# Regulators_and_Buck_Converters.net
KiCad netlist of a schematic drawn in Altium Designer
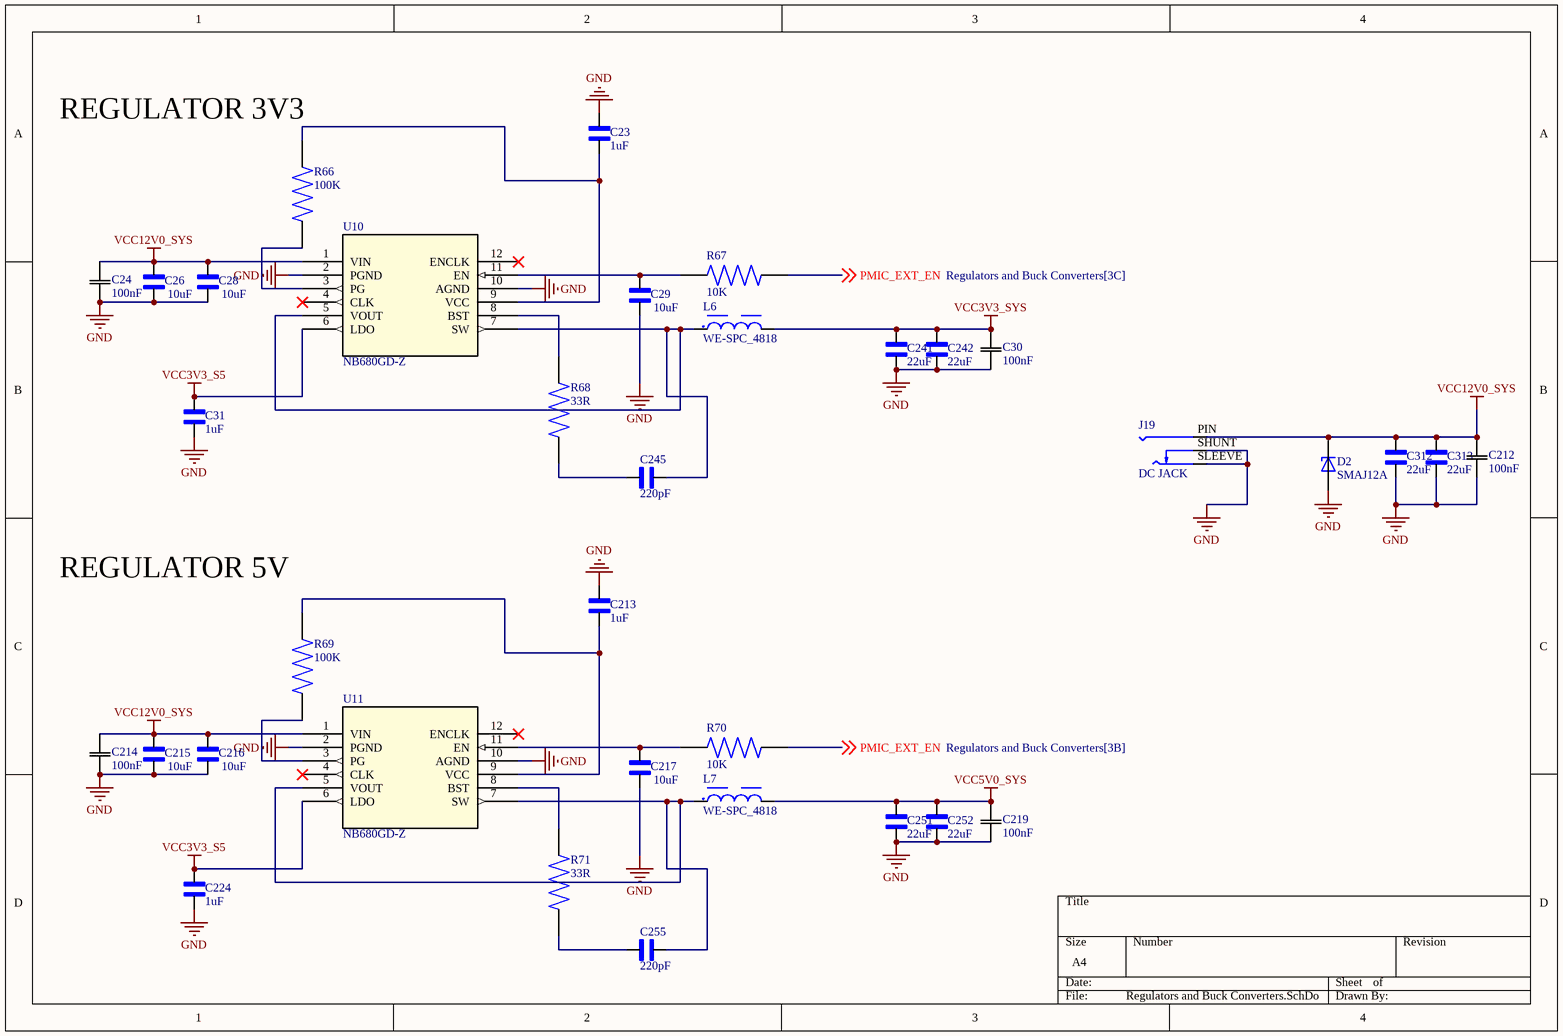
[diagram p0: Regulators and Buck Converters.SchDoc]

(export (version "E")
  (design (tool "Eeschema 10.0.6"))
  (components
    (comp (ref "C23")
      (value "1uF")
      (footprint "CAPC1005X56N")
      (description "1 ÂµF Â±10% 10V Ceramic Capacitor X5R 0402 (1005 Metric)")
      (fields (field (name "MF") "AVX") (field (name "MP") "0402ZD105KAT4A"))
      (libsource (lib "0402ZD105KAT4A") (part "0402ZD105KAT4A"))
    )
    (comp (ref "C24")
      (value "100nF")
      (footprint "CAP_1005_TDK")
      (description "Description")
      (fields
        (field (name "MANUFACTURER_PART_NUMBER") "C1005X7R1H104M050BB")
        (field (name "COPYRIGHT") "Copyright (C) 2025 Ultra Librarian. All rights reserved.")
      )
      (libsource (lib "C1005X7R1H104M050BB") (part "C1005X7R1H104M050BB"))
    )
    (comp (ref "C26")
      (value "10uF")
      (footprint "CAPC1005X70N")
      (description "10 ÂµF Â±20% 6.3V Ceramic Capacitor X5R 0402 (1005 Metric)")
      (fields (field (name "MF") "Samsung") (field (name "MP") "CL05A106MQ5NUNC"))
      (libsource (lib "CL05A106MQ5NUNC") (part "CL05A106MQ5NUNC"))
    )
    (comp (ref "C28")
      (value "10uF")
      (footprint "CAPC1005X70N")
      (description "10 ÂµF Â±20% 6.3V Ceramic Capacitor X5R 0402 (1005 Metric)")
      (fields (field (name "MF") "Samsung") (field (name "MP") "CL05A106MQ5NUNC"))
      (libsource (lib "CL05A106MQ5NUNC") (part "CL05A106MQ5NUNC"))
    )
    (comp (ref "C29")
      (value "10uF")
      (footprint "CAPC1005X70N")
      (description "10 ÂµF Â±20% 6.3V Ceramic Capacitor X5R 0402 (1005 Metric)")
      (fields (field (name "MF") "Samsung") (field (name "MP") "CL05A106MQ5NUNC"))
      (libsource (lib "CL05A106MQ5NUNC") (part "CL05A106MQ5NUNC"))
    )
    (comp (ref "C30")
      (value "100nF")
      (footprint "CAP_1005_TDK")
      (description "Description")
      (fields
        (field (name "MANUFACTURER_PART_NUMBER") "C1005X7R1H104M050BB")
        (field (name "COPYRIGHT") "Copyright (C) 2025 Ultra Librarian. All rights reserved.")
      )
      (libsource (lib "C1005X7R1H104M050BB") (part "C1005X7R1H104M050BB"))
    )
    (comp (ref "C31")
      (value "1uF")
      (footprint "CAPC1005X56N")
      (description "1 ÂµF Â±10% 10V Ceramic Capacitor X5R 0402 (1005 Metric)")
      (fields (field (name "MF") "AVX") (field (name "MP") "0402ZD105KAT4A"))
      (libsource (lib "0402ZD105KAT4A") (part "0402ZD105KAT4A"))
    )
    (comp (ref "C212")
      (value "100nF")
      (footprint "CAP_1005_TDK")
      (description "Description")
      (fields
        (field (name "MANUFACTURER_PART_NUMBER") "C1005X7R1H104M050BB")
        (field (name "COPYRIGHT") "Copyright (C) 2025 Ultra Librarian. All rights reserved.")
      )
      (libsource (lib "C1005X7R1H104M050BB") (part "C1005X7R1H104M050BB"))
    )
    (comp (ref "C213")
      (value "1uF")
      (footprint "CAPC1005X56N")
      (description "1 ÂµF Â±10% 10V Ceramic Capacitor X5R 0402 (1005 Metric)")
      (fields (field (name "MF") "AVX") (field (name "MP") "0402ZD105KAT4A"))
      (libsource (lib "0402ZD105KAT4A") (part "0402ZD105KAT4A"))
    )
    (comp (ref "C214")
      (value "100nF")
      (footprint "CAP_1005_TDK")
      (description "Description")
      (fields
        (field (name "MANUFACTURER_PART_NUMBER") "C1005X7R1H104M050BB")
        (field (name "COPYRIGHT") "Copyright (C) 2025 Ultra Librarian. All rights reserved.")
      )
      (libsource (lib "C1005X7R1H104M050BB") (part "C1005X7R1H104M050BB"))
    )
    (comp (ref "C215")
      (value "10uF")
      (footprint "CAPC1005X70N")
      (description "10 ÂµF Â±20% 6.3V Ceramic Capacitor X5R 0402 (1005 Metric)")
      (fields (field (name "MF") "Samsung") (field (name "MP") "CL05A106MQ5NUNC"))
      (libsource (lib "CL05A106MQ5NUNC") (part "CL05A106MQ5NUNC"))
    )
    (comp (ref "C216")
      (value "10uF")
      (footprint "CAPC1005X70N")
      (description "10 ÂµF Â±20% 6.3V Ceramic Capacitor X5R 0402 (1005 Metric)")
      (fields (field (name "MF") "Samsung") (field (name "MP") "CL05A106MQ5NUNC"))
      (libsource (lib "CL05A106MQ5NUNC") (part "CL05A106MQ5NUNC"))
    )
    (comp (ref "C217")
      (value "10uF")
      (footprint "CAPC1005X70N")
      (description "10 ÂµF Â±20% 6.3V Ceramic Capacitor X5R 0402 (1005 Metric)")
      (fields (field (name "MF") "Samsung") (field (name "MP") "CL05A106MQ5NUNC"))
      (libsource (lib "CL05A106MQ5NUNC") (part "CL05A106MQ5NUNC"))
    )
    (comp (ref "C219")
      (value "100nF")
      (footprint "CAP_1005_TDK")
      (description "Description")
      (fields
        (field (name "MANUFACTURER_PART_NUMBER") "C1005X7R1H104M050BB")
        (field (name "COPYRIGHT") "Copyright (C) 2025 Ultra Librarian. All rights reserved.")
      )
      (libsource (lib "C1005X7R1H104M050BB") (part "C1005X7R1H104M050BB"))
    )
    (comp (ref "C224")
      (value "1uF")
      (footprint "CAPC1005X56N")
      (description "1 ÂµF Â±10% 10V Ceramic Capacitor X5R 0402 (1005 Metric)")
      (fields (field (name "MF") "AVX") (field (name "MP") "0402ZD105KAT4A"))
      (libsource (lib "0402ZD105KAT4A") (part "0402ZD105KAT4A"))
    )
    (comp (ref "C241")
      (value "22uF")
      (footprint "CAPC2012X140N")
      (description "Capacitor, Ceramic, Cap, 22.0pF, Tol 5%, SMT, 50V, C0G ¦ KEMET C0805C220J5GACTU")
      (fields (field (name "MF") "KEMET") (field (name "MP") "C0805C220J5GACTU"))
      (libsource (lib "C0805C220J5GACTU") (part "C0805C220J5GACTU"))
    )
    (comp (ref "C242")
      (value "22uF")
      (footprint "CAPC2012X140N")
      (description "Capacitor, Ceramic, Cap, 22.0pF, Tol 5%, SMT, 50V, C0G ¦ KEMET C0805C220J5GACTU")
      (fields (field (name "MF") "KEMET") (field (name "MP") "C0805C220J5GACTU"))
      (libsource (lib "C0805C220J5GACTU") (part "C0805C220J5GACTU"))
    )
    (comp (ref "C245")
      (value "220pF")
      (footprint "CAPC1608X90")
      (description "220 pF Â±10% 16V Ceramic Capacitor X7R 0603 (1608 Metric)")
      (fields (field (name "MF") "Yageo") (field (name "MP") "CC0603KRX7R7BB221"))
      (libsource (lib "CC0603KRX7R7BB221") (part "CC0603KRX7R7BB221"))
    )
    (comp (ref "C251")
      (value "22uF")
      (footprint "CAPC2012X140N")
      (description "Capacitor, Ceramic, Cap, 22.0pF, Tol 5%, SMT, 50V, C0G ¦ KEMET C0805C220J5GACTU")
      (fields (field (name "MF") "KEMET") (field (name "MP") "C0805C220J5GACTU"))
      (libsource (lib "C0805C220J5GACTU") (part "C0805C220J5GACTU"))
    )
    (comp (ref "C252")
      (value "22uF")
      (footprint "CAPC2012X140N")
      (description "Capacitor, Ceramic, Cap, 22.0pF, Tol 5%, SMT, 50V, C0G ¦ KEMET C0805C220J5GACTU")
      (fields (field (name "MF") "KEMET") (field (name "MP") "C0805C220J5GACTU"))
      (libsource (lib "C0805C220J5GACTU") (part "C0805C220J5GACTU"))
    )
    (comp (ref "C255")
      (value "220pF")
      (footprint "CAPC1608X90")
      (description "220 pF Â±10% 16V Ceramic Capacitor X7R 0603 (1608 Metric)")
      (fields (field (name "MF") "Yageo") (field (name "MP") "CC0603KRX7R7BB221"))
      (libsource (lib "CC0603KRX7R7BB221") (part "CC0603KRX7R7BB221"))
    )
    (comp (ref "C312")
      (value "22uF")
      (footprint "CAPC2012X140N")
      (description "Capacitor, Ceramic, Cap, 22.0pF, Tol 5%, SMT, 50V, C0G ¦ KEMET C0805C220J5GACTU")
      (fields (field (name "MF") "KEMET") (field (name "MP") "C0805C220J5GACTU"))
      (libsource (lib "C0805C220J5GACTU") (part "C0805C220J5GACTU"))
    )
    (comp (ref "C313")
      (value "22uF")
      (footprint "CAPC2012X140N")
      (description "Capacitor, Ceramic, Cap, 22.0pF, Tol 5%, SMT, 50V, C0G ¦ KEMET C0805C220J5GACTU")
      (fields (field (name "MF") "KEMET") (field (name "MP") "C0805C220J5GACTU"))
      (libsource (lib "C0805C220J5GACTU") (part "C0805C220J5GACTU"))
    )
    (comp (ref "D2")
      (value "SMAJ12A")
      (footprint "DIOM4325X250N")
      (description "400W, 14V, 5%, Unidirectional, TVS")
      (fields (field (name "MF") "Taiwan Semiconductor"))
      (libsource (lib "SMAJ12A") (part "SMAJ12A"))
    )
    (comp (ref "J19")
      (value "DC JACK")
      (footprint "SWITCHCRAFT_RASM712PX")
      (description "Conn;AV;DC,Power;Jack;2.5mmPinSize;RtAngle;DCSeries;SMTMount ¦ Switchcraft RASM712PX")
      (fields (field (name "MF") "Switchcraft Inc.") (field (name "MP") "RASM712PX"))
      (libsource (lib "RASM712PX") (part "RASM712PX"))
    )
    (comp (ref "L6")
      (value "WE-SPC_4818")
      (footprint "WE-SPC_4818")
      (description "10 ÂµH Shielded Drum Core, Wirewound Inductor 900 mA 248mOhm Max 1919 (4848 Metric)")
      (fields (field (name "MF") "WÃ¼rth Elektronik") (field (name "MP") "74408941100"))
      (libsource (lib "WE-SPC_4818") (part "WE-SPC_4818"))
    )
    (comp (ref "L7")
      (value "WE-SPC_4818")
      (footprint "WE-SPC_4818")
      (description "10 ÂµH Shielded Drum Core, Wirewound Inductor 900 mA 248mOhm Max 1919 (4848 Metric)")
      (fields (field (name "MF") "WÃ¼rth Elektronik") (field (name "MP") "74408941100"))
      (libsource (lib "WE-SPC_4818") (part "WE-SPC_4818"))
    )
    (comp (ref "R66")
      (value "100K")
      (footprint "RES_ERA3ARB103V")
      (fields (field (name "MP") "ERA3ARB103V"))
      (libsource (lib "ERA3ARB103V") (part "ERA3ARB103V"))
    )
    (comp (ref "R67")
      (value "10K")
      (footprint "RES_ERA3ARB103V")
      (fields (field (name "MP") "ERA3ARB103V"))
      (libsource (lib "ERA3ARB103V") (part "ERA3ARB103V"))
    )
    (comp (ref "R68")
      (value "33R")
      (footprint "RES_ERA6AHD330V")
      (fields (field (name "MP") "ERA6AHD330V"))
      (libsource (lib "ERA6AHD330V") (part "ERA6AHD330V"))
    )
    (comp (ref "R69")
      (value "100K")
      (footprint "RES_ERA3ARB103V")
      (fields (field (name "MP") "ERA3ARB103V"))
      (libsource (lib "ERA3ARB103V") (part "ERA3ARB103V"))
    )
    (comp (ref "R70")
      (value "10K")
      (footprint "RES_ERA3ARB103V")
      (fields (field (name "MP") "ERA3ARB103V"))
      (libsource (lib "ERA3ARB103V") (part "ERA3ARB103V"))
    )
    (comp (ref "R71")
      (value "33R")
      (footprint "RES_ERA6AHD330V")
      (fields (field (name "MP") "ERA6AHD330V"))
      (libsource (lib "ERA6AHD330V") (part "ERA6AHD330V"))
    )
    (comp (ref "U10")
      (value "NB680GD-Z")
      (footprint "QFN-12_NB680_MNP")
      (description "Wide Vin 4.8-26V Low Iq High Current Fixed 3.3V-8A Synchronous Buck Converter with 100mA LDO")
      (fields (field (name "COPYRIGHT") "Copyright (C) 2026 Ultra Librarian. All rights reserved."))
      (libsource (lib "NB680GD-Z") (part "NB680GD-Z"))
    )
    (comp (ref "U11")
      (value "NB680GD-Z")
      (footprint "QFN-12_NB680_MNP")
      (description "Wide Vin 4.8-26V Low Iq High Current Fixed 3.3V-8A Synchronous Buck Converter with 100mA LDO")
      (fields (field (name "COPYRIGHT") "Copyright (C) 2026 Ultra Librarian. All rights reserved."))
      (libsource (lib "NB680GD-Z") (part "NB680GD-Z"))
    )
  )
  (nets
    (net (code "1") (name "GND") (class "Default")
      (node (ref "C212") (pin "1") (pinfunction "1_1") (pintype "passive"))
      (node (ref "C213") (pin "2") (pinfunction "2_2") (pintype "passive"))
      (node (ref "C214") (pin "1") (pinfunction "1_1") (pintype "passive"))
      (node (ref "C215") (pin "1") (pinfunction "1_1") (pintype "passive"))
      (node (ref "C216") (pin "1") (pinfunction "1_1") (pintype "passive"))
      (node (ref "C217") (pin "1") (pinfunction "1_1") (pintype "passive"))
      (node (ref "C219") (pin "1") (pinfunction "1_1") (pintype "passive"))
      (node (ref "C224") (pin "1") (pinfunction "1_1") (pintype "passive"))
      (node (ref "C23") (pin "2") (pinfunction "2_2") (pintype "passive"))
      (node (ref "C24") (pin "1") (pinfunction "1_1") (pintype "passive"))
      (node (ref "C241") (pin "2") (pinfunction "2_2") (pintype "passive"))
      (node (ref "C242") (pin "2") (pinfunction "2_2") (pintype "passive"))
      (node (ref "C251") (pin "2") (pinfunction "2_2") (pintype "passive"))
      (node (ref "C252") (pin "2") (pinfunction "2_2") (pintype "passive"))
      (node (ref "C26") (pin "1") (pinfunction "1_1") (pintype "passive"))
      (node (ref "C28") (pin "1") (pinfunction "1_1") (pintype "passive"))
      (node (ref "C29") (pin "1") (pinfunction "1_1") (pintype "passive"))
      (node (ref "C30") (pin "1") (pinfunction "1_1") (pintype "passive"))
      (node (ref "C31") (pin "1") (pinfunction "1_1") (pintype "passive"))
      (node (ref "C312") (pin "2") (pinfunction "2_2") (pintype "passive"))
      (node (ref "C313") (pin "2") (pinfunction "2_2") (pintype "passive"))
      (node (ref "D2") (pin "A") (pinfunction "A_A") (pintype "passive"))
      (node (ref "J19") (pin "SHUNT") (pinfunction "SHUNT_SHUNT") (pintype "passive"))
      (node (ref "J19") (pin "SLEEVE") (pinfunction "SLEEVE_SLEEVE") (pintype "passive"))
      (node (ref "U10") (pin "10") (pinfunction "AGND_10") (pintype "power_in"))
      (node (ref "U10") (pin "2") (pinfunction "PGND_2") (pintype "power_in"))
      (node (ref "U11") (pin "10") (pinfunction "AGND_10") (pintype "power_in"))
      (node (ref "U11") (pin "2") (pinfunction "PGND_2") (pintype "power_in"))
    )
    (net (code "2") (name "Net-(C245-Pad2)") (class "Default")
      (node (ref "C245") (pin "2") (pinfunction "2_2") (pintype "passive"))
      (node (ref "R68") (pin "1") (pinfunction "1_1") (pintype "passive"))
    )
    (net (code "3") (name "Net-(C255-Pad2)") (class "Default")
      (node (ref "C255") (pin "2") (pinfunction "2_2") (pintype "passive"))
      (node (ref "R71") (pin "1") (pinfunction "1_1") (pintype "passive"))
    )
    (net (code "4") (name "Net-(U10-BST)") (class "Default")
      (node (ref "R68") (pin "2") (pinfunction "2_2") (pintype "passive"))
      (node (ref "U10") (pin "8") (pinfunction "BST_8") (pintype "power_in"))
    )
    (net (code "5") (name "Net-(U10-EN)") (class "Default")
      (node (ref "C29") (pin "2") (pinfunction "2_2") (pintype "passive"))
      (node (ref "R67") (pin "1") (pinfunction "1_1") (pintype "passive"))
      (node (ref "U10") (pin "11") (pinfunction "EN_11") (pintype "input"))
    )
    (net (code "6") (name "Net-(U10-PG)") (class "Default")
      (node (ref "R66") (pin "1") (pinfunction "1_1") (pintype "passive"))
      (node (ref "U10") (pin "3") (pinfunction "PG_3") (pintype "output"))
    )
    (net (code "7") (name "Net-(U10-SW)") (class "Default")
      (node (ref "C245") (pin "1") (pinfunction "1_1") (pintype "passive"))
      (node (ref "L6") (pin "1") (pinfunction "1_1") (pintype "passive"))
      (node (ref "U10") (pin "5") (pinfunction "VOUT_5") (pintype "power_in"))
      (node (ref "U10") (pin "7") (pinfunction "SW_7") (pintype "output"))
    )
    (net (code "8") (name "Net-(U10-VCC)") (class "Default")
      (node (ref "C23") (pin "1") (pinfunction "1_1") (pintype "passive"))
      (node (ref "R66") (pin "2") (pinfunction "2_2") (pintype "passive"))
      (node (ref "U10") (pin "9") (pinfunction "VCC_9") (pintype "power_in"))
    )
    (net (code "9") (name "Net-(U11-BST)") (class "Default")
      (node (ref "R71") (pin "2") (pinfunction "2_2") (pintype "passive"))
      (node (ref "U11") (pin "8") (pinfunction "BST_8") (pintype "power_in"))
    )
    (net (code "10") (name "Net-(U11-EN)") (class "Default")
      (node (ref "C217") (pin "2") (pinfunction "2_2") (pintype "passive"))
      (node (ref "R70") (pin "1") (pinfunction "1_1") (pintype "passive"))
      (node (ref "U11") (pin "11") (pinfunction "EN_11") (pintype "input"))
    )
    (net (code "11") (name "Net-(U11-PG)") (class "Default")
      (node (ref "R69") (pin "1") (pinfunction "1_1") (pintype "passive"))
      (node (ref "U11") (pin "3") (pinfunction "PG_3") (pintype "output"))
    )
    (net (code "12") (name "Net-(U11-SW)") (class "Default")
      (node (ref "C255") (pin "1") (pinfunction "1_1") (pintype "passive"))
      (node (ref "L7") (pin "1") (pinfunction "1_1") (pintype "passive"))
      (node (ref "U11") (pin "5") (pinfunction "VOUT_5") (pintype "power_in"))
      (node (ref "U11") (pin "7") (pinfunction "SW_7") (pintype "output"))
    )
    (net (code "13") (name "Net-(U11-VCC)") (class "Default")
      (node (ref "C213") (pin "1") (pinfunction "1_1") (pintype "passive"))
      (node (ref "R69") (pin "2") (pinfunction "2_2") (pintype "passive"))
      (node (ref "U11") (pin "9") (pinfunction "VCC_9") (pintype "power_in"))
    )
    (net (code "14") (name "PMIC_EXT_EN") (class "Default")
      (node (ref "R67") (pin "2") (pinfunction "2_2") (pintype "passive"))
      (node (ref "R70") (pin "2") (pinfunction "2_2") (pintype "passive"))
    )
    (net (code "15") (name "VCC3V3_S5") (class "Default")
      (node (ref "C224") (pin "2") (pinfunction "2_2") (pintype "passive"))
      (node (ref "C31") (pin "2") (pinfunction "2_2") (pintype "passive"))
      (node (ref "U10") (pin "6") (pinfunction "LDO_6") (pintype "output"))
      (node (ref "U11") (pin "6") (pinfunction "LDO_6") (pintype "output"))
    )
    (net (code "16") (name "VCC3V3_SYS") (class "Default")
      (node (ref "C241") (pin "1") (pinfunction "1_1") (pintype "passive"))
      (node (ref "C242") (pin "1") (pinfunction "1_1") (pintype "passive"))
      (node (ref "C30") (pin "2") (pinfunction "2_2") (pintype "passive"))
      (node (ref "L6") (pin "2") (pinfunction "2_2") (pintype "passive"))
    )
    (net (code "17") (name "VCC5V0_SYS") (class "Default")
      (node (ref "C219") (pin "2") (pinfunction "2_2") (pintype "passive"))
      (node (ref "C251") (pin "1") (pinfunction "1_1") (pintype "passive"))
      (node (ref "C252") (pin "1") (pinfunction "1_1") (pintype "passive"))
      (node (ref "L7") (pin "2") (pinfunction "2_2") (pintype "passive"))
    )
    (net (code "18") (name "VCC12V0_SYS") (class "Default")
      (node (ref "C212") (pin "2") (pinfunction "2_2") (pintype "passive"))
      (node (ref "C214") (pin "2") (pinfunction "2_2") (pintype "passive"))
      (node (ref "C215") (pin "2") (pinfunction "2_2") (pintype "passive"))
      (node (ref "C216") (pin "2") (pinfunction "2_2") (pintype "passive"))
      (node (ref "C24") (pin "2") (pinfunction "2_2") (pintype "passive"))
      (node (ref "C26") (pin "2") (pinfunction "2_2") (pintype "passive"))
      (node (ref "C28") (pin "2") (pinfunction "2_2") (pintype "passive"))
      (node (ref "C312") (pin "1") (pinfunction "1_1") (pintype "passive"))
      (node (ref "C313") (pin "1") (pinfunction "1_1") (pintype "passive"))
      (node (ref "D2") (pin "C") (pinfunction "C_C") (pintype "passive"))
      (node (ref "J19") (pin "PIN") (pinfunction "PIN_PIN") (pintype "passive"))
      (node (ref "U10") (pin "1") (pinfunction "VIN_1") (pintype "power_in"))
      (node (ref "U11") (pin "1") (pinfunction "VIN_1") (pintype "power_in"))
    )
    (net (code "19") (name "unconnected-(U10-CLK-Pad4)") (class "Default")
      (node (ref "U10") (pin "4") (pinfunction "CLK_4") (pintype "output+no_connect"))
    )
    (net (code "20") (name "unconnected-(U10-ENCLK-Pad12)") (class "Default")
      (node (ref "U10") (pin "12") (pinfunction "ENCLK_12") (pintype "passive+no_connect"))
    )
    (net (code "21") (name "unconnected-(U11-CLK-Pad4)") (class "Default")
      (node (ref "U11") (pin "4") (pinfunction "CLK_4") (pintype "output+no_connect"))
    )
    (net (code "22") (name "unconnected-(U11-ENCLK-Pad12)") (class "Default")
      (node (ref "U11") (pin "12") (pinfunction "ENCLK_12") (pintype "passive+no_connect"))
    )
  )
)
